# dcb_lite_logic.net
KiCad netlist of a schematic drawn in Altium Designer
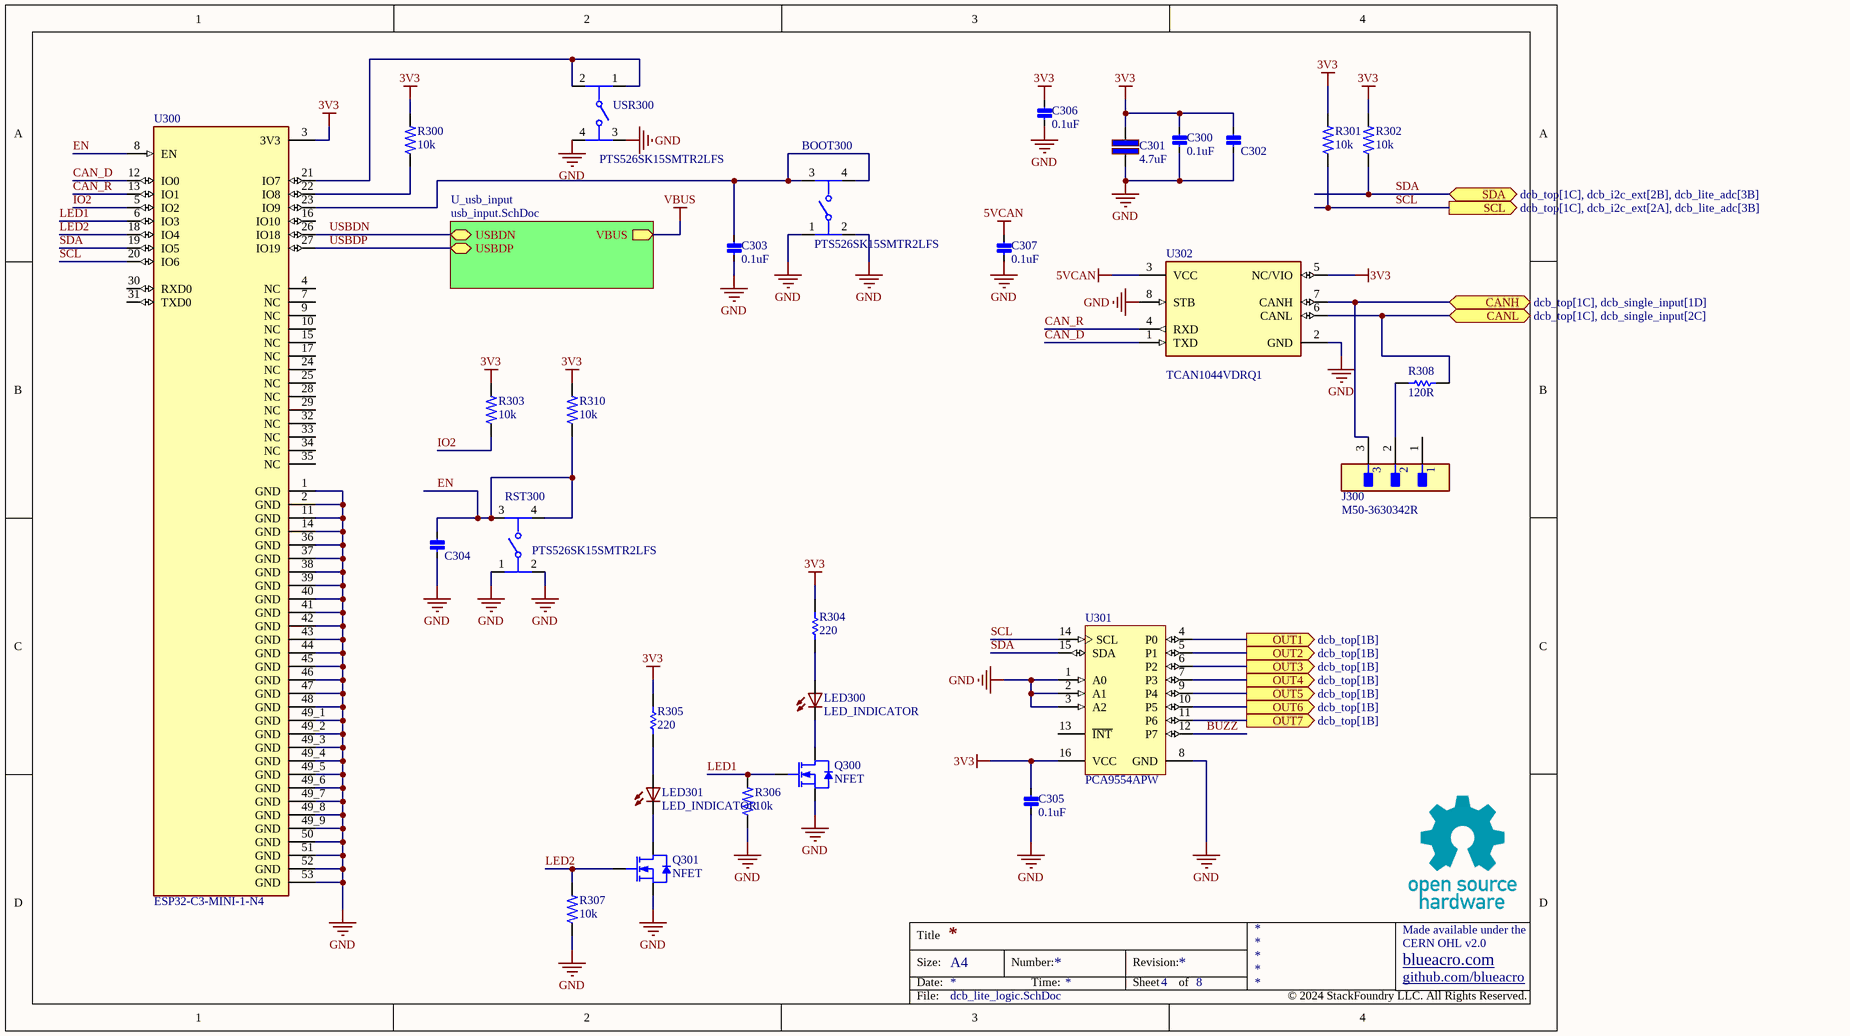
[diagram p0: dcb_lite_logic.SchDoc]

(export (version "E")
  (design (tool "Eeschema 10.0.6"))
  (components
    (comp (ref "BOOT300")
      (value "PTS526SK15SMTR2LFS")
      (footprint "FP-PTS526SK15SMTR2LFS-MFG")
      (description "Switch Tactile N.O. SPST Round Button Gull Wing 0.05A 12VDC 200000Cycles 2.45N SMD T/R")
      (libsource (lib "StackFoundry LLC") (part "b8895f3f4cefb76e1819d2863dba89b"))
    )
    (comp (ref "C300")
      (value "0.1uF")
      (footprint "FP-CL10-IPC_B")
      (description "Cap Ceramic 0.1uF 50V X7R 20% SMD 0603 125C Paper T/R")
      (fields (field (name "VOLTAGE") "50V") (field (name "Comment") "CAP 0.1uF 50V X7R 0603"))
      (libsource (lib "StackFoundry LLC") (part "C-EU"))
    )
    (comp (ref "C301")
      (value "4.7uF")
      (footprint "CAPC3225X20N")
      (description "CAP CER 4.7UF 50V X7R 1210")
      (fields (field (name "VOLTAGE") "50V") (field (name "TOLERANCE") "10%"))
      (libsource (lib "StackFoundry LLC") (part "4.7uF"))
    )
    (comp (ref "C302")
      (value "CAP 1uF 10V X7R 0603")
      (footprint "FP-CL10-IPC_B")
      (description "Cap Ceramic 1uF 10V X7R 10% SMD 0603 125C Paper T/R")
      (libsource (lib "StackFoundry LLC") (part "C-EU"))
    )
    (comp (ref "C303")
      (value "0.1uF")
      (footprint "FP-CL10-IPC_B")
      (description "Cap Ceramic 0.1uF 50V X7R 20% SMD 0603 125C Paper T/R")
      (fields (field (name "VOLTAGE") "50V") (field (name "Comment") "CAP 0.1uF 50V X7R 0603"))
      (libsource (lib "StackFoundry LLC") (part "C-EU"))
    )
    (comp (ref "C304")
      (value "CAP 1uF 10V X7R 0603")
      (footprint "FP-CL10-IPC_B")
      (description "Cap Ceramic 1uF 10V X7R 10% SMD 0603 125C Paper T/R")
      (libsource (lib "StackFoundry LLC") (part "C-EU"))
    )
    (comp (ref "C305")
      (value "0.1uF")
      (footprint "FP-CL10-IPC_B")
      (description "Cap Ceramic 0.1uF 50V X7R 20% SMD 0603 125C Paper T/R")
      (fields (field (name "VOLTAGE") "50V") (field (name "Comment") "CAP 0.1uF 50V X7R 0603"))
      (libsource (lib "StackFoundry LLC") (part "C-EU"))
    )
    (comp (ref "C306")
      (value "0.1uF")
      (footprint "FP-CL10-IPC_B")
      (description "Cap Ceramic 0.1uF 50V X7R 20% SMD 0603 125C Paper T/R")
      (fields (field (name "VOLTAGE") "50V") (field (name "Comment") "CAP 0.1uF 50V X7R 0603"))
      (libsource (lib "StackFoundry LLC") (part "C-EU"))
    )
    (comp (ref "C307")
      (value "0.1uF")
      (footprint "FP-CL10-IPC_B")
      (description "Cap Ceramic 0.1uF 50V X7R 20% SMD 0603 125C Paper T/R")
      (fields (field (name "VOLTAGE") "50V") (field (name "Comment") "CAP 0.1uF 50V X7R 0603"))
      (libsource (lib "StackFoundry LLC") (part "C-EU"))
    )
    (comp (ref "J300")
      (value "M50-3630342R")
      (footprint "FP-M50-3630342R-MFG")
      (description "3 Pos. Male SIL Vertical SMT Conn. RoHS Compliant: Yes")
      (libsource (lib "StackFoundry LLC") (part "0d3f023dd272f625e17a2be33dea85f"))
    )
    (comp (ref "LED300")
      (value "LED_INDICATOR")
      (footprint "LED5MM")
      (libsource (lib "StackFoundry LLC") (part "LED_INDICATOR"))
    )
    (comp (ref "LED301")
      (value "LED_INDICATOR")
      (footprint "LED5MM")
      (libsource (lib "StackFoundry LLC") (part "LED_INDICATOR"))
    )
    (comp (ref "Q300")
      (value "NFET")
      (footprint "SOT23-3")
      (libsource (lib "StackFoundry LLC") (part "NFET"))
    )
    (comp (ref "Q301")
      (value "NFET")
      (footprint "SOT23-3")
      (libsource (lib "StackFoundry LLC") (part "NFET"))
    )
    (comp (ref "R300")
      (value "10k")
      (footprint "RESC1608-IPC-ML")
      (description "Res General Purpose Thick Film 0603 10K Ohm 1% 1/10W ±100ppm/°C Molded SMD Paper T/R")
      (fields (field (name "Comment") "10K 0603 1%"))
      (libsource (lib "StackFoundry LLC") (part "R-US"))
    )
    (comp (ref "R301")
      (value "10k")
      (footprint "RESC1608-IPC-ML")
      (description "Res General Purpose Thick Film 0603 10K Ohm 1% 1/10W ±100ppm/°C Molded SMD Paper T/R")
      (fields (field (name "Comment") "10K 0603 1%"))
      (libsource (lib "StackFoundry LLC") (part "R-US"))
    )
    (comp (ref "R302")
      (value "10k")
      (footprint "RESC1608-IPC-ML")
      (description "Res General Purpose Thick Film 0603 10K Ohm 1% 1/10W ±100ppm/°C Molded SMD Paper T/R")
      (fields (field (name "Comment") "10K 0603 1%"))
      (libsource (lib "StackFoundry LLC") (part "R-US"))
    )
    (comp (ref "R303")
      (value "10k")
      (footprint "RESC1608-IPC-ML")
      (description "Res General Purpose Thick Film 0603 10K Ohm 1% 1/10W ±100ppm/°C Molded SMD Paper T/R")
      (fields (field (name "Comment") "10K 0603 1%"))
      (libsource (lib "StackFoundry LLC") (part "R-US"))
    )
    (comp (ref "R304")
      (value "220")
      (footprint "RESC1608-IPC-ML")
      (fields (field (name "TOLERANCE") "5%") (field (name "Comment") "220R 0603 5%"))
      (libsource (lib "StackFoundry LLC") (part "RES-2"))
    )
    (comp (ref "R305")
      (value "220")
      (footprint "RESC1608-IPC-ML")
      (fields (field (name "TOLERANCE") "5%") (field (name "Comment") "220R 0603 5%"))
      (libsource (lib "StackFoundry LLC") (part "RES-2"))
    )
    (comp (ref "R306")
      (value "10k")
      (footprint "RESC1608-IPC-ML")
      (description "Res General Purpose Thick Film 0603 10K Ohm 1% 1/10W ±100ppm/°C Molded SMD Paper T/R")
      (fields (field (name "Comment") "10K 0603 1%"))
      (libsource (lib "StackFoundry LLC") (part "R-US"))
    )
    (comp (ref "R307")
      (value "10k")
      (footprint "RESC1608-IPC-ML")
      (description "Res General Purpose Thick Film 0603 10K Ohm 1% 1/10W ±100ppm/°C Molded SMD Paper T/R")
      (fields (field (name "Comment") "10K 0603 1%"))
      (libsource (lib "StackFoundry LLC") (part "R-US"))
    )
    (comp (ref "R308")
      (value "120R")
      (footprint "RESC3225X70X50LL20T20")
      (description "SMD Chip Resistor, 120 Ohm, ± 5%, 500 mW, 1210 [3225 Metric], Thick Film, General Purpose")
      (fields (field (name "TOLERANCE") "5%") (field (name "Comment") "120R 1210 5%"))
      (libsource (lib "StackFoundry LLC") (part "RES"))
    )
    (comp (ref "R310")
      (value "10k")
      (footprint "RESC1608-IPC-ML")
      (description "Res General Purpose Thick Film 0603 10K Ohm 1% 1/10W ±100ppm/°C Molded SMD Paper T/R")
      (fields (field (name "Comment") "10K 0603 1%"))
      (libsource (lib "StackFoundry LLC") (part "R-US"))
    )
    (comp (ref "RST300")
      (value "PTS526SK15SMTR2LFS")
      (footprint "FP-PTS526SK15SMTR2LFS-MFG")
      (description "Switch Tactile N.O. SPST Round Button Gull Wing 0.05A 12VDC 200000Cycles 2.45N SMD T/R")
      (libsource (lib "StackFoundry LLC") (part "b8895f3f4cefb76e1819d2863dba89b"))
    )
    (comp (ref "U300")
      (value "ESP32-C3-MINI-1-N4")
      (footprint "XCVR_ESP32-C3-MINI-1-N4")
      (fields (field (name "MF") "Espressif Systems"))
      (libsource (lib "StackFoundry LLC") (part "ESP32-C3-MINI-1-N4"))
    )
    (comp (ref "U301")
      (value "PCA9554APW")
      (footprint "PW0016A_L")
      (description "I2C/SMBus Interface 100kHz/400kHz 5.5V 16-Pin TSSOP Tube / IC I/O EXPANDER I2C 8B 16TSSOP")
      (libsource (lib "StackFoundry LLC") (part "TI-PCA9554A-TSSOP_PW-16"))
    )
    (comp (ref "U302")
      (value "TCAN1044VDRQ1")
      (footprint "FP-D0008A-IPC_B")
      (description "R-PDSO-G8 TCAN1044 Tape & Reel (TR) CAN interface transceiver 100mV 4.905mm 5Mbps -40C~125C TA")
      (libsource (lib "StackFoundry LLC") (part "37286c69b09cf1f90c6308c73223085"))
    )
    (comp (ref "USR300")
      (value "PTS526SK15SMTR2LFS")
      (footprint "FP-PTS526SK15SMTR2LFS-MFG")
      (description "Switch Tactile N.O. SPST Round Button Gull Wing 0.05A 12VDC 200000Cycles 2.45N SMD T/R")
      (libsource (lib "StackFoundry LLC") (part "b8895f3f4cefb76e1819d2863dba89b"))
    )
  )
  (nets
    (net (code "1") (name "/BUZZ") (class "Default")
      (node (ref "U301") (pin "12") (pinfunction "P7_12") (pintype "bidirectional"))
    )
    (net (code "2") (name "/CANH") (class "Default")
      (node (ref "J300") (pin "3") (pinfunction "3_3") (pintype "passive"))
      (node (ref "U302") (pin "7") (pinfunction "CANH_7") (pintype "bidirectional"))
    )
    (net (code "3") (name "/CANL") (class "Default")
      (node (ref "R308") (pin "2") (pinfunction "2_2") (pintype "passive"))
      (node (ref "U302") (pin "6") (pinfunction "CANL_6") (pintype "bidirectional"))
    )
    (net (code "4") (name "/CAN_D") (class "Default")
      (node (ref "U300") (pin "12") (pinfunction "IO0_12") (pintype "bidirectional"))
      (node (ref "U302") (pin "1") (pinfunction "TXD_1") (pintype "input"))
    )
    (net (code "5") (name "/CAN_R") (class "Default")
      (node (ref "U300") (pin "13") (pinfunction "IO1_13") (pintype "bidirectional"))
      (node (ref "U302") (pin "4") (pinfunction "RXD_4") (pintype "output"))
    )
    (net (code "6") (name "/EN") (class "Default")
      (node (ref "C304") (pin "1") (pinfunction "1_1") (pintype "passive"))
      (node (ref "R310") (pin "1") (pinfunction "1_1") (pintype "passive"))
      (node (ref "RST300") (pin "3") (pinfunction "3_3") (pintype "passive"))
      (node (ref "RST300") (pin "4") (pinfunction "4_4") (pintype "passive"))
      (node (ref "U300") (pin "8") (pinfunction "EN_8") (pintype "input"))
    )
    (net (code "7") (name "/IO2") (class "Default")
      (node (ref "R303") (pin "1") (pinfunction "1_1") (pintype "passive"))
      (node (ref "U300") (pin "5") (pinfunction "IO2_5") (pintype "bidirectional"))
    )
    (net (code "8") (name "/LED1") (class "Default")
      (node (ref "Q300") (pin "1") (pinfunction "G_1") (pintype "passive"))
      (node (ref "R306") (pin "2") (pinfunction "2_2") (pintype "passive"))
      (node (ref "U300") (pin "6") (pinfunction "IO3_6") (pintype "bidirectional"))
    )
    (net (code "9") (name "/LED2") (class "Default")
      (node (ref "Q301") (pin "1") (pinfunction "G_1") (pintype "passive"))
      (node (ref "R307") (pin "2") (pinfunction "2_2") (pintype "passive"))
      (node (ref "U300") (pin "18") (pinfunction "IO4_18") (pintype "bidirectional"))
    )
    (net (code "10") (name "/OUT1") (class "Default")
      (node (ref "U301") (pin "4") (pinfunction "P0_4") (pintype "bidirectional"))
    )
    (net (code "11") (name "/OUT2") (class "Default")
      (node (ref "U301") (pin "5") (pinfunction "P1_5") (pintype "bidirectional"))
    )
    (net (code "12") (name "/OUT3") (class "Default")
      (node (ref "U301") (pin "6") (pinfunction "P2_6") (pintype "bidirectional"))
    )
    (net (code "13") (name "/OUT4") (class "Default")
      (node (ref "U301") (pin "7") (pinfunction "P3_7") (pintype "bidirectional"))
    )
    (net (code "14") (name "/OUT5") (class "Default")
      (node (ref "U301") (pin "9") (pinfunction "P4_9") (pintype "bidirectional"))
    )
    (net (code "15") (name "/OUT6") (class "Default")
      (node (ref "U301") (pin "10") (pinfunction "P5_10") (pintype "bidirectional"))
    )
    (net (code "16") (name "/OUT7") (class "Default")
      (node (ref "U301") (pin "11") (pinfunction "P6_11") (pintype "bidirectional"))
    )
    (net (code "17") (name "/SCL") (class "Default")
      (node (ref "R301") (pin "1") (pinfunction "1_1") (pintype "passive"))
      (node (ref "U300") (pin "20") (pinfunction "IO6_20") (pintype "bidirectional"))
      (node (ref "U301") (pin "14") (pinfunction "SCL_14") (pintype "input"))
    )
    (net (code "18") (name "/SDA") (class "Default")
      (node (ref "R302") (pin "1") (pinfunction "1_1") (pintype "passive"))
      (node (ref "U300") (pin "19") (pinfunction "IO5_19") (pintype "bidirectional"))
      (node (ref "U301") (pin "15") (pinfunction "SDA_15") (pintype "bidirectional"))
    )
    (net (code "19") (name "/USBDN") (class "Default")
      (node (ref "U300") (pin "26") (pinfunction "IO18_26") (pintype "bidirectional"))
    )
    (net (code "20") (name "/USBDP") (class "Default")
      (node (ref "U300") (pin "27") (pinfunction "IO19_27") (pintype "bidirectional"))
    )
    (net (code "21") (name "3V3") (class "Default")
      (node (ref "C300") (pin "1") (pinfunction "1_1") (pintype "passive"))
      (node (ref "C301") (pin "2") (pintype "passive"))
      (node (ref "C302") (pin "1") (pinfunction "1_1") (pintype "passive"))
      (node (ref "C305") (pin "1") (pinfunction "1_1") (pintype "passive"))
      (node (ref "C306") (pin "1") (pinfunction "1_1") (pintype "passive"))
      (node (ref "R300") (pin "2") (pinfunction "2_2") (pintype "passive"))
      (node (ref "R301") (pin "2") (pinfunction "2_2") (pintype "passive"))
      (node (ref "R302") (pin "2") (pinfunction "2_2") (pintype "passive"))
      (node (ref "R303") (pin "2") (pinfunction "2_2") (pintype "passive"))
      (node (ref "R304") (pin "2") (pinfunction "2_2") (pintype "passive"))
      (node (ref "R305") (pin "2") (pinfunction "2_2") (pintype "passive"))
      (node (ref "R310") (pin "2") (pinfunction "2_2") (pintype "passive"))
      (node (ref "U300") (pin "3") (pinfunction "3V3_3") (pintype "power_in"))
      (node (ref "U301") (pin "16") (pinfunction "VCC_16") (pintype "power_in"))
      (node (ref "U302") (pin "5") (pinfunction "NC/VIO_5") (pintype "bidirectional"))
    )
    (net (code "22") (name "5VCAN") (class "Default")
      (node (ref "C307") (pin "1") (pinfunction "1_1") (pintype "passive"))
      (node (ref "U302") (pin "3") (pinfunction "VCC_3") (pintype "power_in"))
    )
    (net (code "23") (name "GND") (class "Default")
      (node (ref "BOOT300") (pin "1") (pinfunction "1_1") (pintype "passive"))
      (node (ref "BOOT300") (pin "2") (pinfunction "2_2") (pintype "passive"))
      (node (ref "C300") (pin "2") (pinfunction "2_2") (pintype "passive"))
      (node (ref "C301") (pin "1") (pintype "passive"))
      (node (ref "C302") (pin "2") (pinfunction "2_2") (pintype "passive"))
      (node (ref "C303") (pin "2") (pinfunction "2_2") (pintype "passive"))
      (node (ref "C304") (pin "2") (pinfunction "2_2") (pintype "passive"))
      (node (ref "C305") (pin "2") (pinfunction "2_2") (pintype "passive"))
      (node (ref "C306") (pin "2") (pinfunction "2_2") (pintype "passive"))
      (node (ref "C307") (pin "2") (pinfunction "2_2") (pintype "passive"))
      (node (ref "Q300") (pin "2") (pinfunction "S_2") (pintype "passive"))
      (node (ref "Q301") (pin "2") (pinfunction "S_2") (pintype "passive"))
      (node (ref "R306") (pin "1") (pinfunction "1_1") (pintype "passive"))
      (node (ref "R307") (pin "1") (pinfunction "1_1") (pintype "passive"))
      (node (ref "RST300") (pin "1") (pinfunction "1_1") (pintype "passive"))
      (node (ref "RST300") (pin "2") (pinfunction "2_2") (pintype "passive"))
      (node (ref "U300") (pin "1") (pinfunction "GND_1") (pintype "power_in"))
      (node (ref "U300") (pin "11") (pinfunction "GND_11") (pintype "power_in"))
      (node (ref "U300") (pin "14") (pinfunction "GND_14") (pintype "power_in"))
      (node (ref "U300") (pin "2") (pinfunction "GND_2") (pintype "power_in"))
      (node (ref "U300") (pin "36") (pinfunction "GND_36") (pintype "power_in"))
      (node (ref "U300") (pin "37") (pinfunction "GND_37") (pintype "power_in"))
      (node (ref "U300") (pin "38") (pinfunction "GND_38") (pintype "power_in"))
      (node (ref "U300") (pin "39") (pinfunction "GND_39") (pintype "power_in"))
      (node (ref "U300") (pin "40") (pinfunction "GND_40") (pintype "power_in"))
      (node (ref "U300") (pin "41") (pinfunction "GND_41") (pintype "power_in"))
      (node (ref "U300") (pin "42") (pinfunction "GND_42") (pintype "power_in"))
      (node (ref "U300") (pin "43") (pinfunction "GND_43") (pintype "power_in"))
      (node (ref "U300") (pin "44") (pinfunction "GND_44") (pintype "power_in"))
      (node (ref "U300") (pin "45") (pinfunction "GND_45") (pintype "power_in"))
      (node (ref "U300") (pin "46") (pinfunction "GND_46") (pintype "power_in"))
      (node (ref "U300") (pin "47") (pinfunction "GND_47") (pintype "power_in"))
      (node (ref "U300") (pin "48") (pinfunction "GND_48") (pintype "power_in"))
      (node (ref "U300") (pin "49_1") (pinfunction "GND_49_1") (pintype "power_in"))
      (node (ref "U300") (pin "49_2") (pinfunction "GND_49_2") (pintype "power_in"))
      (node (ref "U300") (pin "49_3") (pinfunction "GND_49_3") (pintype "power_in"))
      (node (ref "U300") (pin "49_4") (pinfunction "GND_49_4") (pintype "power_in"))
      (node (ref "U300") (pin "49_5") (pinfunction "GND_49_5") (pintype "power_in"))
      (node (ref "U300") (pin "49_6") (pinfunction "GND_49_6") (pintype "power_in"))
      (node (ref "U300") (pin "49_7") (pinfunction "GND_49_7") (pintype "power_in"))
      (node (ref "U300") (pin "49_8") (pinfunction "GND_49_8") (pintype "power_in"))
      (node (ref "U300") (pin "49_9") (pinfunction "GND_49_9") (pintype "power_in"))
      (node (ref "U300") (pin "50") (pinfunction "GND_50") (pintype "power_in"))
      (node (ref "U300") (pin "51") (pinfunction "GND_51") (pintype "power_in"))
      (node (ref "U300") (pin "52") (pinfunction "GND_52") (pintype "power_in"))
      (node (ref "U300") (pin "53") (pinfunction "GND_53") (pintype "power_in"))
      (node (ref "U301") (pin "1") (pinfunction "A0_1") (pintype "input"))
      (node (ref "U301") (pin "2") (pinfunction "A1_2") (pintype "input"))
      (node (ref "U301") (pin "3") (pinfunction "A2_3") (pintype "input"))
      (node (ref "U301") (pin "8") (pinfunction "GND_8") (pintype "power_in"))
      (node (ref "U302") (pin "2") (pinfunction "GND_2") (pintype "power_in"))
      (node (ref "U302") (pin "8") (pinfunction "STB_8") (pintype "input"))
      (node (ref "USR300") (pin "3") (pinfunction "3_3") (pintype "passive"))
      (node (ref "USR300") (pin "4") (pinfunction "4_4") (pintype "passive"))
    )
    (net (code "24") (name "Net-(J300-Pad2)") (class "Default")
      (node (ref "J300") (pin "2") (pinfunction "2_2") (pintype "passive"))
      (node (ref "R308") (pin "1") (pinfunction "1_1") (pintype "passive"))
    )
    (net (code "25") (name "Net-(LED300-PadA)") (class "Default")
      (node (ref "LED300") (pin "A") (pinfunction "A_A") (pintype "passive"))
      (node (ref "R304") (pin "1") (pinfunction "1_1") (pintype "passive"))
    )
    (net (code "26") (name "Net-(LED301-PadA)") (class "Default")
      (node (ref "LED301") (pin "A") (pinfunction "A_A") (pintype "passive"))
      (node (ref "R305") (pin "1") (pinfunction "1_1") (pintype "passive"))
    )
    (net (code "27") (name "Net-(Q300-D)") (class "Default")
      (node (ref "LED300") (pin "C") (pinfunction "C_C") (pintype "passive"))
      (node (ref "Q300") (pin "3") (pinfunction "D_3") (pintype "passive"))
    )
    (net (code "28") (name "Net-(Q301-D)") (class "Default")
      (node (ref "LED301") (pin "C") (pinfunction "C_C") (pintype "passive"))
      (node (ref "Q301") (pin "3") (pinfunction "D_3") (pintype "passive"))
    )
    (net (code "29") (name "Net-(U300-IO7)") (class "Default")
      (node (ref "U300") (pin "21") (pinfunction "IO7_21") (pintype "bidirectional"))
      (node (ref "USR300") (pin "1") (pinfunction "1_1") (pintype "passive"))
      (node (ref "USR300") (pin "2") (pinfunction "2_2") (pintype "passive"))
    )
    (net (code "30") (name "Net-(U300-IO8)") (class "Default")
      (node (ref "R300") (pin "1") (pinfunction "1_1") (pintype "passive"))
      (node (ref "U300") (pin "22") (pinfunction "IO8_22") (pintype "bidirectional"))
    )
    (net (code "31") (name "Net-(U300-IO9)") (class "Default")
      (node (ref "BOOT300") (pin "3") (pinfunction "3_3") (pintype "passive"))
      (node (ref "BOOT300") (pin "4") (pinfunction "4_4") (pintype "passive"))
      (node (ref "C303") (pin "1") (pinfunction "1_1") (pintype "passive"))
      (node (ref "U300") (pin "23") (pinfunction "IO9_23") (pintype "bidirectional"))
    )
    (net (code "33") (name "unconnected-(J300-Pad1)") (class "Default")
      (node (ref "J300") (pin "1") (pinfunction "1_1") (pintype "passive"))
    )
    (net (code "34") (name "unconnected-(U300-IO10-Pad16)") (class "Default")
      (node (ref "U300") (pin "16") (pinfunction "IO10_16") (pintype "bidirectional"))
    )
    (net (code "35") (name "unconnected-(U300-NC-Pad4)") (class "Default")
      (node (ref "U300") (pin "4") (pinfunction "NC_4") (pintype "passive"))
    )
    (net (code "36") (name "unconnected-(U300-NC-Pad7)") (class "Default")
      (node (ref "U300") (pin "7") (pinfunction "NC_7") (pintype "passive"))
    )
    (net (code "37") (name "unconnected-(U300-NC-Pad9)") (class "Default")
      (node (ref "U300") (pin "9") (pinfunction "NC_9") (pintype "passive"))
    )
    (net (code "38") (name "unconnected-(U300-NC-Pad10)") (class "Default")
      (node (ref "U300") (pin "10") (pinfunction "NC_10") (pintype "passive"))
    )
    (net (code "39") (name "unconnected-(U300-NC-Pad15)") (class "Default")
      (node (ref "U300") (pin "15") (pinfunction "NC_15") (pintype "passive"))
    )
    (net (code "40") (name "unconnected-(U300-NC-Pad17)") (class "Default")
      (node (ref "U300") (pin "17") (pinfunction "NC_17") (pintype "passive"))
    )
    (net (code "41") (name "unconnected-(U300-NC-Pad24)") (class "Default")
      (node (ref "U300") (pin "24") (pinfunction "NC_24") (pintype "passive"))
    )
    (net (code "42") (name "unconnected-(U300-NC-Pad25)") (class "Default")
      (node (ref "U300") (pin "25") (pinfunction "NC_25") (pintype "passive"))
    )
    (net (code "43") (name "unconnected-(U300-NC-Pad28)") (class "Default")
      (node (ref "U300") (pin "28") (pinfunction "NC_28") (pintype "passive"))
    )
    (net (code "44") (name "unconnected-(U300-NC-Pad29)") (class "Default")
      (node (ref "U300") (pin "29") (pinfunction "NC_29") (pintype "passive"))
    )
    (net (code "45") (name "unconnected-(U300-NC-Pad32)") (class "Default")
      (node (ref "U300") (pin "32") (pinfunction "NC_32") (pintype "passive"))
    )
    (net (code "46") (name "unconnected-(U300-NC-Pad33)") (class "Default")
      (node (ref "U300") (pin "33") (pinfunction "NC_33") (pintype "passive"))
    )
    (net (code "47") (name "unconnected-(U300-NC-Pad34)") (class "Default")
      (node (ref "U300") (pin "34") (pinfunction "NC_34") (pintype "passive"))
    )
    (net (code "48") (name "unconnected-(U300-NC-Pad35)") (class "Default")
      (node (ref "U300") (pin "35") (pinfunction "NC_35") (pintype "passive"))
    )
    (net (code "49") (name "unconnected-(U300-RXD0-Pad30)") (class "Default")
      (node (ref "U300") (pin "30") (pinfunction "RXD0_30") (pintype "bidirectional"))
    )
    (net (code "50") (name "unconnected-(U300-TXD0-Pad31)") (class "Default")
      (node (ref "U300") (pin "31") (pinfunction "TXD0_31") (pintype "bidirectional"))
    )
    (net (code "51") (name "unconnected-(U301-~{INT}-Pad13)") (class "Default")
      (node (ref "U301") (pin "13") (pinfunction "~{INT}_13") (pintype "open_collector"))
    )
  )
)
